# ESP32_Accelerometer.net
KiCad netlist of a schematic drawn in Altium Designer
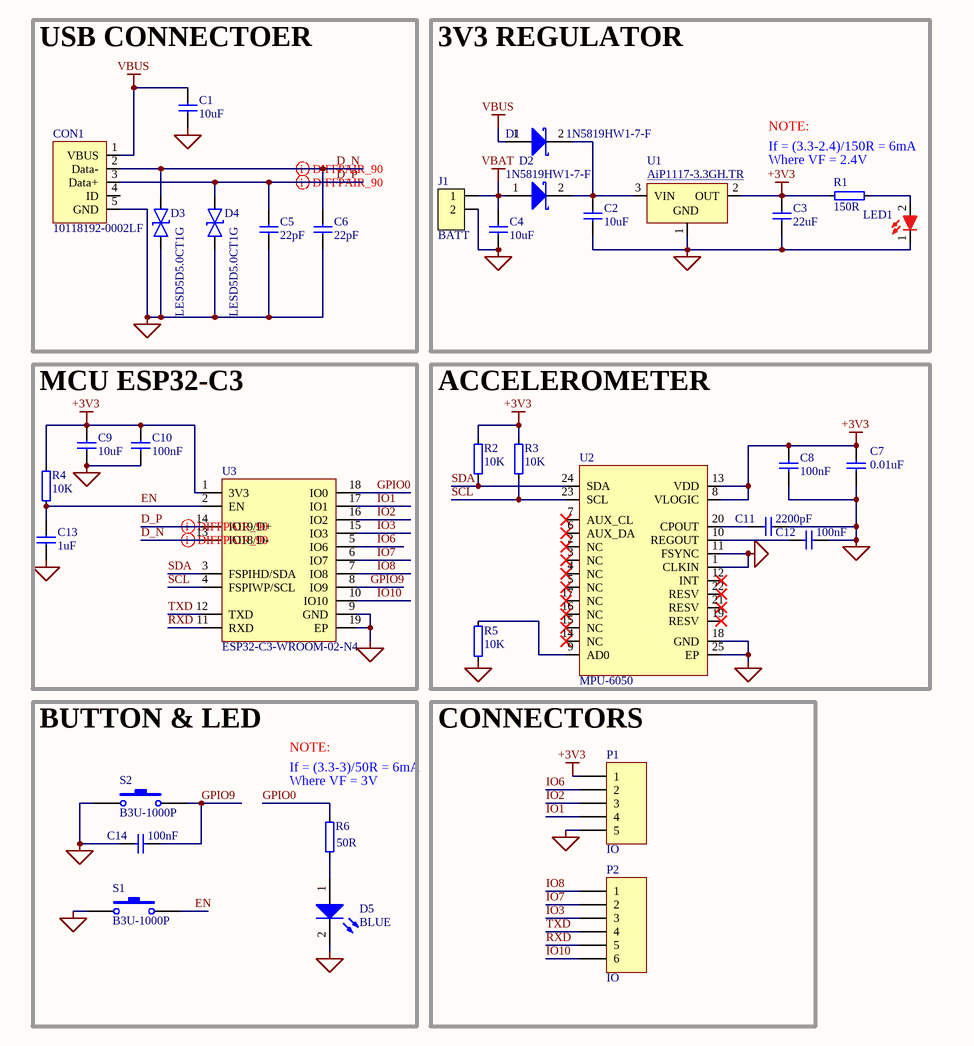
[diagram p0: ESP32_Accelerometer.SchDoc]

(export (version "E")
  (design (tool "Eeschema 10.0.6"))
  (components
    (comp (ref "C1")
      (value "10uF")
      (footprint "CAPC1608X06L")
      (description "Capacitor, X5R, ±5%, 6.3V")
      (libsource (lib "AltiumLib") (part "CAP"))
    )
    (comp (ref "C2")
      (value "10uF")
      (footprint "CAPC1608X06L")
      (description "Capacitor, X5R, ±5%, 6.3V")
      (libsource (lib "AltiumLib") (part "CAP"))
    )
    (comp (ref "C3")
      (value "22uF")
      (footprint "CAPC1608X06L")
      (description "Capacitor, X5R, ±5%, 6.3V")
      (libsource (lib "AltiumLib") (part "CAP"))
    )
    (comp (ref "C4")
      (value "10uF")
      (footprint "CAPC1608X06L")
      (description "Capacitor, X5R, ±5%, 6.3V")
      (libsource (lib "AltiumLib") (part "CAP"))
    )
    (comp (ref "C5")
      (value "22pF")
      (footprint "CAPC1005X04L")
      (description "Capacitor, X5R, ±5%, 6.3V")
      (libsource (lib "AltiumLib") (part "CAP"))
    )
    (comp (ref "C6")
      (value "22pF")
      (footprint "CAPC1005X04L")
      (description "Capacitor, X5R, ±5%, 6.3V")
      (libsource (lib "AltiumLib") (part "CAP"))
    )
    (comp (ref "C7")
      (value "0.01uF")
      (footprint "CAPC1005X04L")
      (description "Capacitor, X5R, ±5%, 6.3V")
      (libsource (lib "AltiumLib") (part "CAP"))
    )
    (comp (ref "C8")
      (value "100nF")
      (footprint "CAPC1005X04L")
      (description "Capacitor, X5R, ±5%, 6.3V")
      (libsource (lib "AltiumLib") (part "CAP"))
    )
    (comp (ref "C9")
      (value "10uF")
      (footprint "CAPC1005X04L")
      (description "Capacitor, X5R, ±5%, 6.3V")
      (libsource (lib "AltiumLib") (part "CAP"))
    )
    (comp (ref "C10")
      (value "100nF")
      (footprint "CAPC1005X04L")
      (description "Capacitor, X5R, ±5%, 6.3V")
      (libsource (lib "AltiumLib") (part "CAP"))
    )
    (comp (ref "C11")
      (value "2200pF")
      (footprint "CAPC1005X04L")
      (description "Capacitor, X5R, ±5%, 6.3V")
      (libsource (lib "AltiumLib") (part "CAP"))
    )
    (comp (ref "C12")
      (value "100nF")
      (footprint "CAPC1005X04L")
      (description "Capacitor, X5R, ±5%, 6.3V")
      (libsource (lib "AltiumLib") (part "CAP"))
    )
    (comp (ref "C13")
      (value "1uF")
      (footprint "CAPC1005X04L")
      (description "Capacitor, X5R, ±5%, 6.3V")
      (libsource (lib "AltiumLib") (part "CAP"))
    )
    (comp (ref "C14")
      (value "100nF")
      (footprint "CAPC1005X04L")
      (description "Capacitor, X5R, ±5%, 6.3V")
      (libsource (lib "AltiumLib") (part "CAP"))
    )
    (comp (ref "CON1")
      (value "10118192-0002LF")
      (footprint "CONN_USB-B-MICRO-SMD-10118192-0002LF")
      (libsource (lib "Symbol") (part "CONN_USB-B-MICRO_SMD"))
    )
    (comp (ref "D1")
      (value "1N5819HW1-7-F")
      (footprint "SOD-123FL")
      (description "Schottky Diode")
      (libsource (lib "Miscellaneous Devices") (part "D Schottky"))
    )
    (comp (ref "D2")
      (value "1N5819HW1-7-F")
      (footprint "SOD-123FL")
      (description "Schottky Diode")
      (libsource (lib "Miscellaneous Devices") (part "D Schottky"))
    )
    (comp (ref "D3")
      (value "LESD5D5.0CT1G")
      (footprint "SOD-523")
      (libsource (lib "Symbol") (part "LESD5D5.0CT1G"))
    )
    (comp (ref "D4")
      (value "LESD5D5.0CT1G")
      (footprint "SOD-523")
      (libsource (lib "Symbol") (part "LESD5D5.0CT1G"))
    )
    (comp (ref "D5")
      (value "BLUE")
      (footprint "LED_SMD_0402-BLUE")
      (description "Typical INFRARED GaAs LED")
      (libsource (lib "Miscellaneous Devices") (part "LED0"))
    )
    (comp (ref "J1")
      (value "BATT")
      (footprint "CONN-TH_B2B-PH-K-S")
      (description "1.0mm pitch connector side entry SMD")
      (fields
        (field (name "PART NUMBER") "SM03B-SRSS-TB")
        (field (name "MANUFACTURER") "JST Sales America Inc.")
      )
      (libsource (lib "AltiumLib") (part "CONN-3"))
    )
    (comp (ref "LED1")
      (value "RED")
      (footprint "LED_SMD-0603")
      (description "LED RED CLEAR SMD")
      (fields
        (field (name "MANUFACTURER") "Vishay Lite-On")
        (field (name "MANUFACTURER PART NUMBER") "LTST-C191KRKT")
      )
      (libsource (lib "Schematic_Lib") (part "LED0603_RED"))
    )
    (comp (ref "P1")
      (value "IO")
      (footprint "CONN_HEADER_5P_2mm")
      (description "Header, 5-Pin")
      (libsource (lib "Miscellaneous Connectors") (part "Header 5"))
    )
    (comp (ref "P2")
      (value "IO")
      (footprint "CONN_HEADER_6P_2mm")
      (description "Header, 6-Pin")
      (libsource (lib "Miscellaneous Connectors") (part "Header 6"))
    )
    (comp (ref "R1")
      (value "150R")
      (footprint "RESC1608X06N")
      (description "Resistor, ±1%, 0.05W")
      (libsource (lib "AltiumLib") (part "RES"))
    )
    (comp (ref "R2")
      (value "10K")
      (footprint "RESC1005X04L_C")
      (description "Resistor, ±1%, 0.05W")
      (libsource (lib "AltiumLib") (part "RES"))
    )
    (comp (ref "R3")
      (value "10K")
      (footprint "RESC1005X04L_C")
      (description "Resistor, ±1%, 0.05W")
      (libsource (lib "AltiumLib") (part "RES"))
    )
    (comp (ref "R4")
      (value "10K")
      (footprint "RESC1005X04L_C")
      (description "Resistor, ±1%, 0.05W")
      (libsource (lib "AltiumLib") (part "RES"))
    )
    (comp (ref "R5")
      (value "10K")
      (footprint "RESC1005X04L_C")
      (description "Resistor, ±1%, 0.05W")
      (libsource (lib "AltiumLib") (part "RES"))
    )
    (comp (ref "R6")
      (value "50R")
      (footprint "RESC1005X04L_C")
      (description "Resistor, ±1%, 0.05W")
      (libsource (lib "AltiumLib") (part "RES"))
    )
    (comp (ref "S1")
      (value "B3U-1000P")
      (footprint "BUTTON-SMD-2.3x3mm_2P_B3U-1000P")
      (description "Switch")
      (libsource (lib "Miscellaneous Devices") (part "SW-PB"))
    )
    (comp (ref "S2")
      (value "B3U-1000P")
      (footprint "BUTTON-SMD-2.3x3mm_2P_B3U-1000P")
      (description "Switch")
      (libsource (lib "Miscellaneous Devices") (part "SW-PB"))
    )
    (comp (ref "U1")
      (value "AiP1117-3.3GH.TR")
      (footprint "SOT-223")
      (libsource (lib "Symbol") (part "AiP1117-3.3"))
    )
    (comp (ref "U2")
      (value "MPU-6050")
      (footprint "QFN-24_4x4mm")
      (libsource (lib "Symbol") (part "MPU-6050"))
    )
    (comp (ref "U3")
      (value "ESP32-C3-WROOM-02-N4")
      (footprint "ESP32-C3-WROOM-02-N4-4MB")
      (libsource (lib "Symbol") (part "ESP32-C3-WROOM-02-N4"))
    )
  )
  (nets
    (net (code "1") (name "+3V3") (class "Default")
      (node (ref "C10") (pin "1") (pinfunction "1_1") (pintype "passive"))
      (node (ref "C3") (pin "1") (pinfunction "1_1") (pintype "passive"))
      (node (ref "C7") (pin "1") (pinfunction "1_1") (pintype "passive"))
      (node (ref "C8") (pin "1") (pinfunction "1_1") (pintype "passive"))
      (node (ref "C9") (pin "1") (pinfunction "1_1") (pintype "passive"))
      (node (ref "P1") (pin "1") (pinfunction "1_1") (pintype "passive"))
      (node (ref "R1") (pin "2") (pinfunction "2_2") (pintype "passive"))
      (node (ref "R2") (pin "2") (pinfunction "2_2") (pintype "passive"))
      (node (ref "R3") (pin "2") (pinfunction "2_2") (pintype "passive"))
      (node (ref "R4") (pin "2") (pinfunction "2_2") (pintype "passive"))
      (node (ref "U1") (pin "2") (pinfunction "OUT_2") (pintype "passive"))
      (node (ref "U2") (pin "13") (pinfunction "VDD_13") (pintype "passive"))
      (node (ref "U2") (pin "8") (pinfunction "VLOGIC_8") (pintype "passive"))
      (node (ref "U3") (pin "1") (pinfunction "3V3_1") (pintype "passive"))
    )
    (net (code "2") (name "/D_N") (class "Default")
      (node (ref "C6") (pin "1") (pinfunction "1_1") (pintype "passive"))
      (node (ref "CON1") (pin "2") (pinfunction "Data-_2") (pintype "passive"))
      (node (ref "D3") (pin "2") (pinfunction "2_2") (pintype "passive"))
      (node (ref "U3") (pin "13") (pinfunction "IO18/D-_13") (pintype "passive"))
    )
    (net (code "3") (name "/D_P") (class "Default")
      (node (ref "C5") (pin "1") (pinfunction "1_1") (pintype "passive"))
      (node (ref "CON1") (pin "3") (pinfunction "Data+_3") (pintype "passive"))
      (node (ref "D4") (pin "2") (pinfunction "2_2") (pintype "passive"))
      (node (ref "U3") (pin "14") (pinfunction "IO19/D+_14") (pintype "passive"))
    )
    (net (code "4") (name "/EN") (class "Default")
      (node (ref "C13") (pin "1") (pinfunction "1_1") (pintype "passive"))
      (node (ref "R4") (pin "1") (pinfunction "1_1") (pintype "passive"))
      (node (ref "S1") (pin "1") (pinfunction "1_1") (pintype "passive"))
      (node (ref "U3") (pin "2") (pinfunction "EN_2") (pintype "passive"))
    )
    (net (code "5") (name "/GPIO0") (class "Default")
      (node (ref "R6") (pin "2") (pinfunction "2_2") (pintype "passive"))
      (node (ref "U3") (pin "18") (pinfunction "IO0_18") (pintype "passive"))
    )
    (net (code "6") (name "/GPIO9") (class "Default")
      (node (ref "C14") (pin "2") (pinfunction "2_2") (pintype "passive"))
      (node (ref "S2") (pin "1") (pinfunction "1_1") (pintype "passive"))
      (node (ref "U3") (pin "8") (pinfunction "IO9_8") (pintype "passive"))
    )
    (net (code "7") (name "/IO1") (class "Default")
      (node (ref "P1") (pin "4") (pinfunction "4_4") (pintype "passive"))
      (node (ref "U3") (pin "17") (pinfunction "IO1_17") (pintype "passive"))
    )
    (net (code "8") (name "/IO2") (class "Default")
      (node (ref "P1") (pin "3") (pinfunction "3_3") (pintype "passive"))
      (node (ref "U3") (pin "16") (pinfunction "IO2_16") (pintype "passive"))
    )
    (net (code "9") (name "/IO3") (class "Default")
      (node (ref "P2") (pin "3") (pinfunction "3_3") (pintype "passive"))
      (node (ref "U3") (pin "15") (pinfunction "IO3_15") (pintype "passive"))
    )
    (net (code "10") (name "/IO6") (class "Default")
      (node (ref "P1") (pin "2") (pinfunction "2_2") (pintype "passive"))
      (node (ref "U3") (pin "5") (pinfunction "IO6_5") (pintype "passive"))
    )
    (net (code "11") (name "/IO7") (class "Default")
      (node (ref "P2") (pin "2") (pinfunction "2_2") (pintype "passive"))
      (node (ref "U3") (pin "6") (pinfunction "IO7_6") (pintype "passive"))
    )
    (net (code "12") (name "/IO8") (class "Default")
      (node (ref "P2") (pin "1") (pinfunction "1_1") (pintype "passive"))
      (node (ref "U3") (pin "7") (pinfunction "IO8_7") (pintype "passive"))
    )
    (net (code "13") (name "/IO10") (class "Default")
      (node (ref "P2") (pin "6") (pinfunction "6_6") (pintype "passive"))
      (node (ref "U3") (pin "10") (pinfunction "IO10_10") (pintype "passive"))
    )
    (net (code "14") (name "/RXD") (class "Default")
      (node (ref "P2") (pin "5") (pinfunction "5_5") (pintype "passive"))
      (node (ref "U3") (pin "11") (pinfunction "RXD_11") (pintype "passive"))
    )
    (net (code "15") (name "/SCL") (class "Default")
      (node (ref "R3") (pin "1") (pinfunction "1_1") (pintype "passive"))
      (node (ref "U2") (pin "23") (pinfunction "SCL_23") (pintype "passive"))
      (node (ref "U3") (pin "4") (pinfunction "FSPIWP/SCL_4") (pintype "passive"))
    )
    (net (code "16") (name "/SDA") (class "Default")
      (node (ref "R2") (pin "1") (pinfunction "1_1") (pintype "passive"))
      (node (ref "U2") (pin "24") (pinfunction "SDA_24") (pintype "passive"))
      (node (ref "U3") (pin "3") (pinfunction "FSPIHD/SDA_3") (pintype "passive"))
    )
    (net (code "17") (name "/TXD") (class "Default")
      (node (ref "P2") (pin "4") (pinfunction "4_4") (pintype "passive"))
      (node (ref "U3") (pin "12") (pinfunction "TXD_12") (pintype "passive"))
    )
    (net (code "18") (name "GND") (class "Default")
      (node (ref "C1") (pin "2") (pinfunction "2_2") (pintype "passive"))
      (node (ref "C10") (pin "2") (pinfunction "2_2") (pintype "passive"))
      (node (ref "C11") (pin "2") (pinfunction "2_2") (pintype "passive"))
      (node (ref "C12") (pin "2") (pinfunction "2_2") (pintype "passive"))
      (node (ref "C13") (pin "2") (pinfunction "2_2") (pintype "passive"))
      (node (ref "C14") (pin "1") (pinfunction "1_1") (pintype "passive"))
      (node (ref "C2") (pin "2") (pinfunction "2_2") (pintype "passive"))
      (node (ref "C3") (pin "2") (pinfunction "2_2") (pintype "passive"))
      (node (ref "C4") (pin "2") (pinfunction "2_2") (pintype "passive"))
      (node (ref "C5") (pin "2") (pinfunction "2_2") (pintype "passive"))
      (node (ref "C6") (pin "2") (pinfunction "2_2") (pintype "passive"))
      (node (ref "C7") (pin "2") (pinfunction "2_2") (pintype "passive"))
      (node (ref "C8") (pin "2") (pinfunction "2_2") (pintype "passive"))
      (node (ref "C9") (pin "2") (pinfunction "2_2") (pintype "passive"))
      (node (ref "CON1") (pin "5") (pinfunction "GND_5") (pintype "passive"))
      (node (ref "D3") (pin "1") (pinfunction "1_1") (pintype "passive"))
      (node (ref "D4") (pin "1") (pinfunction "1_1") (pintype "passive"))
      (node (ref "D5") (pin "2") (pinfunction "K_2") (pintype "passive"))
      (node (ref "J1") (pin "2") (pinfunction "2_2") (pintype "passive"))
      (node (ref "LED1") (pin "1") (pinfunction "K_1") (pintype "passive"))
      (node (ref "P1") (pin "5") (pinfunction "5_5") (pintype "passive"))
      (node (ref "R5") (pin "2") (pinfunction "2_2") (pintype "passive"))
      (node (ref "S1") (pin "2") (pinfunction "2_2") (pintype "passive"))
      (node (ref "S2") (pin "2") (pinfunction "2_2") (pintype "passive"))
      (node (ref "U1") (pin "1") (pinfunction "GND_1") (pintype "passive"))
      (node (ref "U2") (pin "1") (pinfunction "CLKIN_1") (pintype "passive"))
      (node (ref "U2") (pin "11") (pinfunction "FSYNC_11") (pintype "passive"))
      (node (ref "U2") (pin "18") (pinfunction "GND_18") (pintype "passive"))
      (node (ref "U2") (pin "25") (pinfunction "EP_25") (pintype "passive"))
      (node (ref "U3") (pin "19") (pinfunction "EP_19") (pintype "passive"))
      (node (ref "U3") (pin "9") (pinfunction "GND_9") (pintype "passive"))
    )
    (net (code "19") (name "Net-(D1-K)") (class "Default")
      (node (ref "C2") (pin "1") (pinfunction "1_1") (pintype "passive"))
      (node (ref "D1") (pin "2") (pinfunction "K_2") (pintype "passive"))
      (node (ref "D2") (pin "2") (pinfunction "K_2") (pintype "passive"))
      (node (ref "U1") (pin "3") (pinfunction "VIN_3") (pintype "passive"))
    )
    (net (code "20") (name "Net-(D5-A)") (class "Default")
      (node (ref "D5") (pin "1") (pinfunction "A_1") (pintype "passive"))
      (node (ref "R6") (pin "1") (pinfunction "1_1") (pintype "passive"))
    )
    (net (code "21") (name "Net-(LED1-A)") (class "Default")
      (node (ref "LED1") (pin "2") (pinfunction "A_2") (pintype "passive"))
      (node (ref "R1") (pin "1") (pinfunction "1_1") (pintype "passive"))
    )
    (net (code "22") (name "Net-(U2-AD0)") (class "Default")
      (node (ref "R5") (pin "1") (pinfunction "1_1") (pintype "passive"))
      (node (ref "U2") (pin "9") (pinfunction "AD0_9") (pintype "passive"))
    )
    (net (code "23") (name "Net-(U2-CPOUT)") (class "Default")
      (node (ref "C11") (pin "1") (pinfunction "1_1") (pintype "passive"))
      (node (ref "U2") (pin "20") (pinfunction "CPOUT_20") (pintype "passive"))
    )
    (net (code "24") (name "Net-(U2-REGOUT)") (class "Default")
      (node (ref "C12") (pin "1") (pinfunction "1_1") (pintype "passive"))
      (node (ref "U2") (pin "10") (pinfunction "REGOUT_10") (pintype "passive"))
    )
    (net (code "25") (name "VBAT") (class "Default")
      (node (ref "C4") (pin "1") (pinfunction "1_1") (pintype "passive"))
      (node (ref "D2") (pin "1") (pinfunction "A_1") (pintype "passive"))
      (node (ref "J1") (pin "1") (pinfunction "1_1") (pintype "passive"))
    )
    (net (code "26") (name "VBUS") (class "Default")
      (node (ref "C1") (pin "1") (pinfunction "1_1") (pintype "passive"))
      (node (ref "CON1") (pin "1") (pinfunction "VBUS_1") (pintype "passive"))
      (node (ref "D1") (pin "1") (pinfunction "A_1") (pintype "passive"))
    )
    (net (code "27") (name "unconnected-(CON1-ID-Pad4)") (class "Default")
      (node (ref "CON1") (pin "4") (pinfunction "ID_4") (pintype "passive"))
    )
    (net (code "28") (name "unconnected-(U2-AUX_CL-Pad7)") (class "Default")
      (node (ref "U2") (pin "7") (pinfunction "AUX_CL_7") (pintype "passive+no_connect"))
    )
    (net (code "29") (name "unconnected-(U2-AUX_DA-Pad6)") (class "Default")
      (node (ref "U2") (pin "6") (pinfunction "AUX_DA_6") (pintype "passive+no_connect"))
    )
    (net (code "30") (name "unconnected-(U2-INT-Pad12)") (class "Default")
      (node (ref "U2") (pin "12") (pinfunction "INT_12") (pintype "passive+no_connect"))
    )
    (net (code "31") (name "unconnected-(U2-NC-Pad2)") (class "Default")
      (node (ref "U2") (pin "2") (pinfunction "NC_2") (pintype "passive+no_connect"))
    )
    (net (code "32") (name "unconnected-(U2-NC-Pad3)") (class "Default")
      (node (ref "U2") (pin "3") (pinfunction "NC_3") (pintype "passive+no_connect"))
    )
    (net (code "33") (name "unconnected-(U2-NC-Pad4)") (class "Default")
      (node (ref "U2") (pin "4") (pinfunction "NC_4") (pintype "passive+no_connect"))
    )
    (net (code "34") (name "unconnected-(U2-NC-Pad5)") (class "Default")
      (node (ref "U2") (pin "5") (pinfunction "NC_5") (pintype "passive+no_connect"))
    )
    (net (code "35") (name "unconnected-(U2-NC-Pad14)") (class "Default")
      (node (ref "U2") (pin "14") (pinfunction "NC_14") (pintype "passive+no_connect"))
    )
    (net (code "36") (name "unconnected-(U2-NC-Pad15)") (class "Default")
      (node (ref "U2") (pin "15") (pinfunction "NC_15") (pintype "passive+no_connect"))
    )
    (net (code "37") (name "unconnected-(U2-NC-Pad16)") (class "Default")
      (node (ref "U2") (pin "16") (pinfunction "NC_16") (pintype "passive+no_connect"))
    )
    (net (code "38") (name "unconnected-(U2-NC-Pad17)") (class "Default")
      (node (ref "U2") (pin "17") (pinfunction "NC_17") (pintype "passive+no_connect"))
    )
    (net (code "39") (name "unconnected-(U2-RESV-Pad19)") (class "Default")
      (node (ref "U2") (pin "19") (pinfunction "RESV_19") (pintype "passive+no_connect"))
    )
    (net (code "40") (name "unconnected-(U2-RESV-Pad21)") (class "Default")
      (node (ref "U2") (pin "21") (pinfunction "RESV_21") (pintype "passive+no_connect"))
    )
    (net (code "41") (name "unconnected-(U2-RESV-Pad22)") (class "Default")
      (node (ref "U2") (pin "22") (pinfunction "RESV_22") (pintype "passive+no_connect"))
    )
  )
)
